# Power.net
KiCad netlist of a schematic drawn in Altium Designer
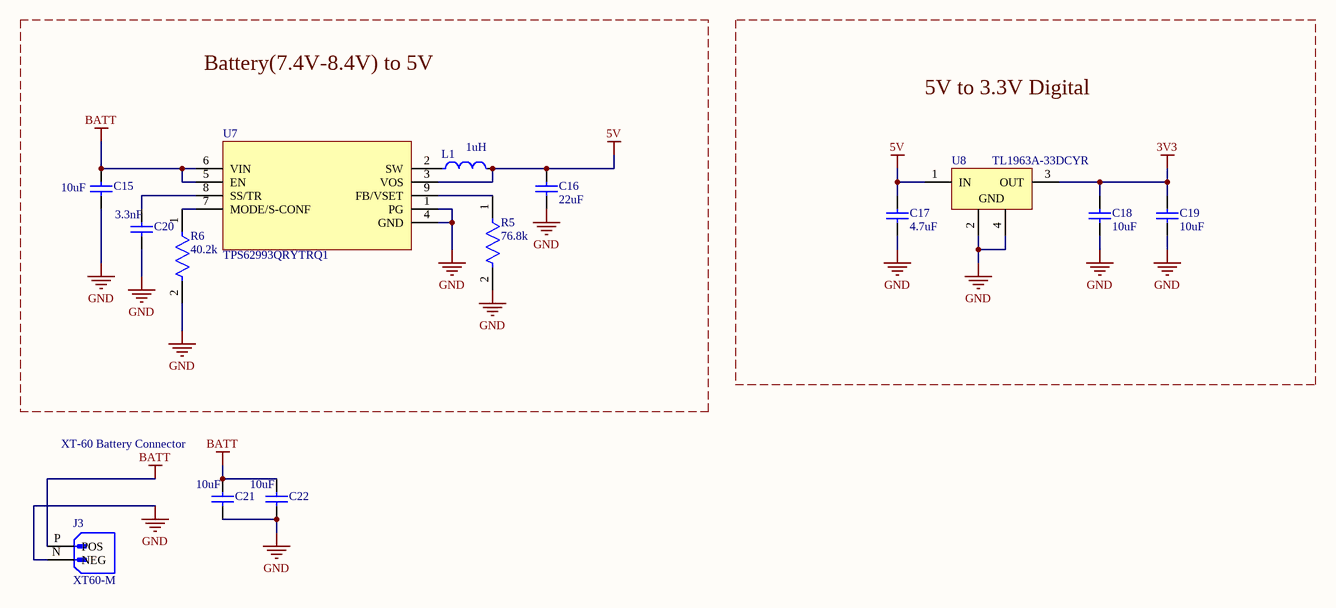
[diagram p0: Power.SchDoc]

(export (version "E")
  (design (tool "Eeschema 10.0.6"))
  (components
    (comp (ref "C15")
      (value "10uF")
      (footprint "0402_C")
      (fields
        (field (name "LCSC PART #") "C315248")
        (field (name "MANUFACTURER") "Samsung Electro-Mechanics")
        (field (name "MANUFACTURER PART NUMBER") "CL05A106MP5NUNC")
      )
      (libsource (lib "Flight_Computer1") (part "C_10uF_0402"))
    )
    (comp (ref "C16")
      (value "22uF")
      (footprint "0402_C")
      (description "CAP CER 22UF 10V X5R 0402")
      (fields
        (field (name "MANUFACTURER") "Murata")
        (field (name "MANUFACTURER PART NUMBER") "GRM158R61A226ME15D")
      )
      (libsource (lib "Flight_Computer1") (part "C_22uF_0402_1"))
    )
    (comp (ref "C17")
      (value "4.7uF")
      (footprint "0402_C")
      (description "CAP CER 4.7UF 16V X5R 0402")
      (fields
        (field (name "MANUFACTURER") "Samsung")
        (field (name "MANUFACTURER PART NUMBER") "CL05A475MO5NUNC")
      )
      (libsource (lib "Flight_Computer1") (part "C_4.7uF_0402"))
    )
    (comp (ref "C18")
      (value "10uF")
      (footprint "0402_C")
      (fields
        (field (name "LCSC PART #") "C315248")
        (field (name "MANUFACTURER") "Samsung Electro-Mechanics")
        (field (name "MANUFACTURER PART NUMBER") "CL05A106MP5NUNC")
      )
      (libsource (lib "Flight_Computer1") (part "C_10uF_0402"))
    )
    (comp (ref "C19")
      (value "10uF")
      (footprint "0402_C")
      (fields
        (field (name "LCSC PART #") "C315248")
        (field (name "MANUFACTURER") "Samsung Electro-Mechanics")
        (field (name "MANUFACTURER PART NUMBER") "CL05A106MP5NUNC")
      )
      (libsource (lib "Flight_Computer1") (part "C_10uF_0402"))
    )
    (comp (ref "C20")
      (value "3.3nF")
      (footprint "0402_C")
      (description "CAP CER 3300PF (3.3nF) 10V X7R 0402")
      (fields
        (field (name "MANUFACTURER") "Samsung Electro-Mechanics")
        (field (name "MANUFACTURER PART NUMBER") "CL05B332KA5VPNC")
      )
      (libsource (lib "Flight_Computer1") (part "C_3.3nF_0402"))
    )
    (comp (ref "C21")
      (value "10uF")
      (footprint "0402_C")
      (fields
        (field (name "LCSC PART #") "C315248")
        (field (name "MANUFACTURER") "Samsung Electro-Mechanics")
        (field (name "MANUFACTURER PART NUMBER") "CL05A106MP5NUNC")
      )
      (libsource (lib "Flight_Computer1") (part "C_10uF_0402"))
    )
    (comp (ref "C22")
      (value "10uF")
      (footprint "0402_C")
      (fields
        (field (name "LCSC PART #") "C315248")
        (field (name "MANUFACTURER") "Samsung Electro-Mechanics")
        (field (name "MANUFACTURER PART NUMBER") "CL05A106MP5NUNC")
      )
      (libsource (lib "Flight_Computer1") (part "C_10uF_0402"))
    )
    (comp (ref "J3")
      (value "XT60-M")
      (footprint "AMASS_XT60-M")
      (description "Plug; DC supply; XT60; male; PIN: 2; for cable; soldered; 30A; 500V")
      (fields (field (name "MF") "AMASS"))
      (libsource (lib "George Evanisko") (part "XT60-M"))
    )
    (comp (ref "L1")
      (value "1uH")
      (footprint "AOTAB201610S3R3101T")
      (description "FIXED IND 1UH 1.7A 128 MOHM SMD")
      (fields
        (field (name "MANUFACTURER") "Murata")
        (field (name "MANUFACTURER PART NUMBER") "DFE201610E-2R2M=P2")
      )
      (libsource (lib "Flight_Computer1") (part "L_1uH_2016"))
    )
    (comp (ref "R5")
      (value "76.8k")
      (footprint "FP-RK73H1J-MFG")
      (description "40.2kΩ ±0.5% 0.1W Chip Resistor 0603 Thick Film AEC-Q200 Qualified\r\nRK73H1JTTD4022D")
      (fields (field (name "TOLERANCE") "0.5%"))
      (libsource (lib "Altium Content Vault") (part "1029c3af85768c4190bb7ad29bc67b5"))
    )
    (comp (ref "R6")
      (value "40.2k")
      (footprint "FP-RK73H1J-MFG")
      (description "40.2kΩ ±0.5% 0.1W Chip Resistor 0603 Thick Film AEC-Q200 Qualified\r\nRK73H1JTTD4022D")
      (fields (field (name "TOLERANCE") "0.5%"))
      (libsource (lib "Altium Content Vault") (part "1029c3af85768c4190bb7ad29bc67b5"))
    )
    (comp (ref "U7")
      (value "TPS62993QRYTRQ1")
      (footprint "RYT0009A-MFG")
      (description "IC REG BUCK ADJ 3A 9VQFN")
      (fields (field (name "MANUFACTURER") "Texas Instruments") (field (name "LCSC PART #") "C5342042"))
      (libsource (lib "Flight_Computer1") (part "TPS62993QRYTRQ1"))
    )
    (comp (ref "U8")
      (value "TL1963A-33DCYR")
      (footprint "SOT230P700X180-4N")
      (description "1.5-A, 20-V, low-dropout voltage regulator with reverse current & reverse voltage protection")
      (fields
        (field (name "MOUSER PART NUMBER") "595-TL1963A-33DCYR")
        (field (name "MANUFACTURER") "Texas Instruments")
      )
      (libsource (lib "Flight_Computer1") (part "TL1963A-33DCYR"))
    )
  )
  (nets
    (net (code "1") (name "3V3") (class "Default")
      (node (ref "C18") (pin "2") (pinfunction "2_2") (pintype "passive"))
      (node (ref "C19") (pin "2") (pinfunction "2_2") (pintype "passive"))
      (node (ref "U8") (pin "3") (pinfunction "OUT_3") (pintype "power_in"))
    )
    (net (code "2") (name "5V") (class "Default")
      (node (ref "C16") (pin "2") (pinfunction "2_2") (pintype "passive"))
      (node (ref "C17") (pin "1") (pinfunction "1_1") (pintype "passive"))
      (node (ref "L1") (pin "2") (pinfunction "2_2") (pintype "passive"))
      (node (ref "U7") (pin "3") (pinfunction "VOS_3") (pintype "passive"))
      (node (ref "U8") (pin "1") (pinfunction "IN_1") (pintype "power_in"))
    )
    (net (code "3") (name "BATT") (class "Default")
      (node (ref "C15") (pin "1") (pinfunction "1_1") (pintype "passive"))
      (node (ref "C21") (pin "1") (pinfunction "1_1") (pintype "passive"))
      (node (ref "C22") (pin "1") (pinfunction "1_1") (pintype "passive"))
      (node (ref "J3") (pin "P") (pinfunction "POS_P") (pintype "passive"))
      (node (ref "U7") (pin "5") (pinfunction "EN_5") (pintype "passive"))
      (node (ref "U7") (pin "6") (pinfunction "VIN_6") (pintype "passive"))
    )
    (net (code "4") (name "GND") (class "Default")
      (node (ref "C15") (pin "2") (pinfunction "2_2") (pintype "passive"))
      (node (ref "C16") (pin "1") (pinfunction "1_1") (pintype "passive"))
      (node (ref "C17") (pin "2") (pinfunction "2_2") (pintype "passive"))
      (node (ref "C18") (pin "1") (pinfunction "1_1") (pintype "passive"))
      (node (ref "C19") (pin "1") (pinfunction "1_1") (pintype "passive"))
      (node (ref "C20") (pin "1") (pinfunction "1_1") (pintype "passive"))
      (node (ref "C21") (pin "2") (pinfunction "2_2") (pintype "passive"))
      (node (ref "C22") (pin "2") (pinfunction "2_2") (pintype "passive"))
      (node (ref "J3") (pin "N") (pinfunction "NEG_N") (pintype "passive"))
      (node (ref "R5") (pin "2") (pinfunction "2_2") (pintype "passive"))
      (node (ref "R6") (pin "2") (pinfunction "2_2") (pintype "passive"))
      (node (ref "U7") (pin "1") (pinfunction "PG_1") (pintype "passive"))
      (node (ref "U7") (pin "4") (pinfunction "GND_4") (pintype "passive"))
      (node (ref "U8") (pin "2") (pinfunction "GND_2") (pintype "power_in"))
      (node (ref "U8") (pin "4") (pinfunction "GND_4") (pintype "power_in"))
    )
    (net (code "5") (name "Net-(U7-FB{slash}VSET)") (class "Default")
      (node (ref "R5") (pin "1") (pinfunction "1_1") (pintype "passive"))
      (node (ref "U7") (pin "9") (pinfunction "FB/VSET_9") (pintype "passive"))
    )
    (net (code "6") (name "Net-(U7-MODE{slash}S-CONF)") (class "Default")
      (node (ref "R6") (pin "1") (pinfunction "1_1") (pintype "passive"))
      (node (ref "U7") (pin "7") (pinfunction "MODE/S-CONF_7") (pintype "passive"))
    )
    (net (code "7") (name "Net-(U7-SS{slash}TR)") (class "Default")
      (node (ref "C20") (pin "2") (pinfunction "2_2") (pintype "passive"))
      (node (ref "U7") (pin "8") (pinfunction "SS/TR_8") (pintype "passive"))
    )
    (net (code "8") (name "Net-(U7-SW)") (class "Default")
      (node (ref "L1") (pin "1") (pinfunction "1_1") (pintype "passive"))
      (node (ref "U7") (pin "2") (pinfunction "SW_2") (pintype "passive"))
    )
  )
)
